# 5p_ATtiny_adapter.net
KiCad netlist of a schematic drawn in EAGLE
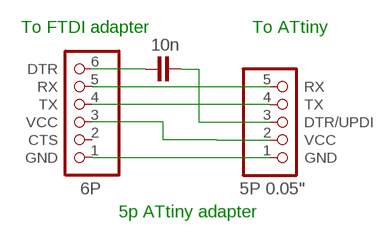
[diagram p0: schematic, sheet 1]

(export (version "E")
  (design (tool "Eeschema 10.0.6"))
  (components
    (comp (ref "C1")
      (value "10n")
      (footprint "eagle-import:0603-SMALL")
      (libsource (lib "eagle-import") (part "SMD-C-0603-SMALL"))
    )
    (comp (ref "J1")
      (value "6P")
      (footprint "eagle-import:1X06")
      (libsource (lib "eagle-import") (part "FTDIHEADER"))
    )
    (comp (ref "J2")
      (value "5P 0.05\"")
      (footprint "eagle-import:FTDI-UPDI-5P")
      (libsource (lib "eagle-import") (part "ZIGZAG-FTDI-UPDI-5P{dblquote}"))
    )
  )
  (nets
    (net (code "1") (name "Net-(J1-DTR)") (class "Default")
      (node (ref "C1") (pin "1") (pinfunction "1_1") (pintype "passive"))
      (node (ref "J1") (pin "6") (pinfunction "DTR_6") (pintype "passive"))
    )
    (net (code "2") (name "Net-(J1-GND)") (class "Default")
      (node (ref "J1") (pin "1") (pinfunction "GND_1") (pintype "passive"))
      (node (ref "J2") (pin "1") (pinfunction "GND_1") (pintype "passive"))
    )
    (net (code "3") (name "Net-(J1-RX)") (class "Default")
      (node (ref "J1") (pin "5") (pinfunction "RX_5") (pintype "passive"))
      (node (ref "J2") (pin "5") (pinfunction "RX_5") (pintype "passive"))
    )
    (net (code "4") (name "Net-(J1-TX)") (class "Default")
      (node (ref "J1") (pin "4") (pinfunction "TX_4") (pintype "passive"))
      (node (ref "J2") (pin "4") (pinfunction "TX_4") (pintype "passive"))
    )
    (net (code "5") (name "Net-(J1-VCC)") (class "Default")
      (node (ref "J1") (pin "3") (pinfunction "VCC_3") (pintype "passive"))
      (node (ref "J2") (pin "2") (pinfunction "VCC_2") (pintype "passive"))
    )
    (net (code "6") (name "Net-(J2-DTR{slash}UPDI)") (class "Default")
      (node (ref "C1") (pin "2") (pinfunction "2_2") (pintype "passive"))
      (node (ref "J2") (pin "3") (pinfunction "DTR/UPDI_3") (pintype "passive"))
    )
    (net (code "7") (name "unconnected-(J1-CTS-Pad2)") (class "Default")
      (node (ref "J1") (pin "2") (pinfunction "CTS_2") (pintype "passive"))
    )
  )
)
